# linobit-coilInputs.net
KiCad netlist of a schematic drawn in Altium Designer
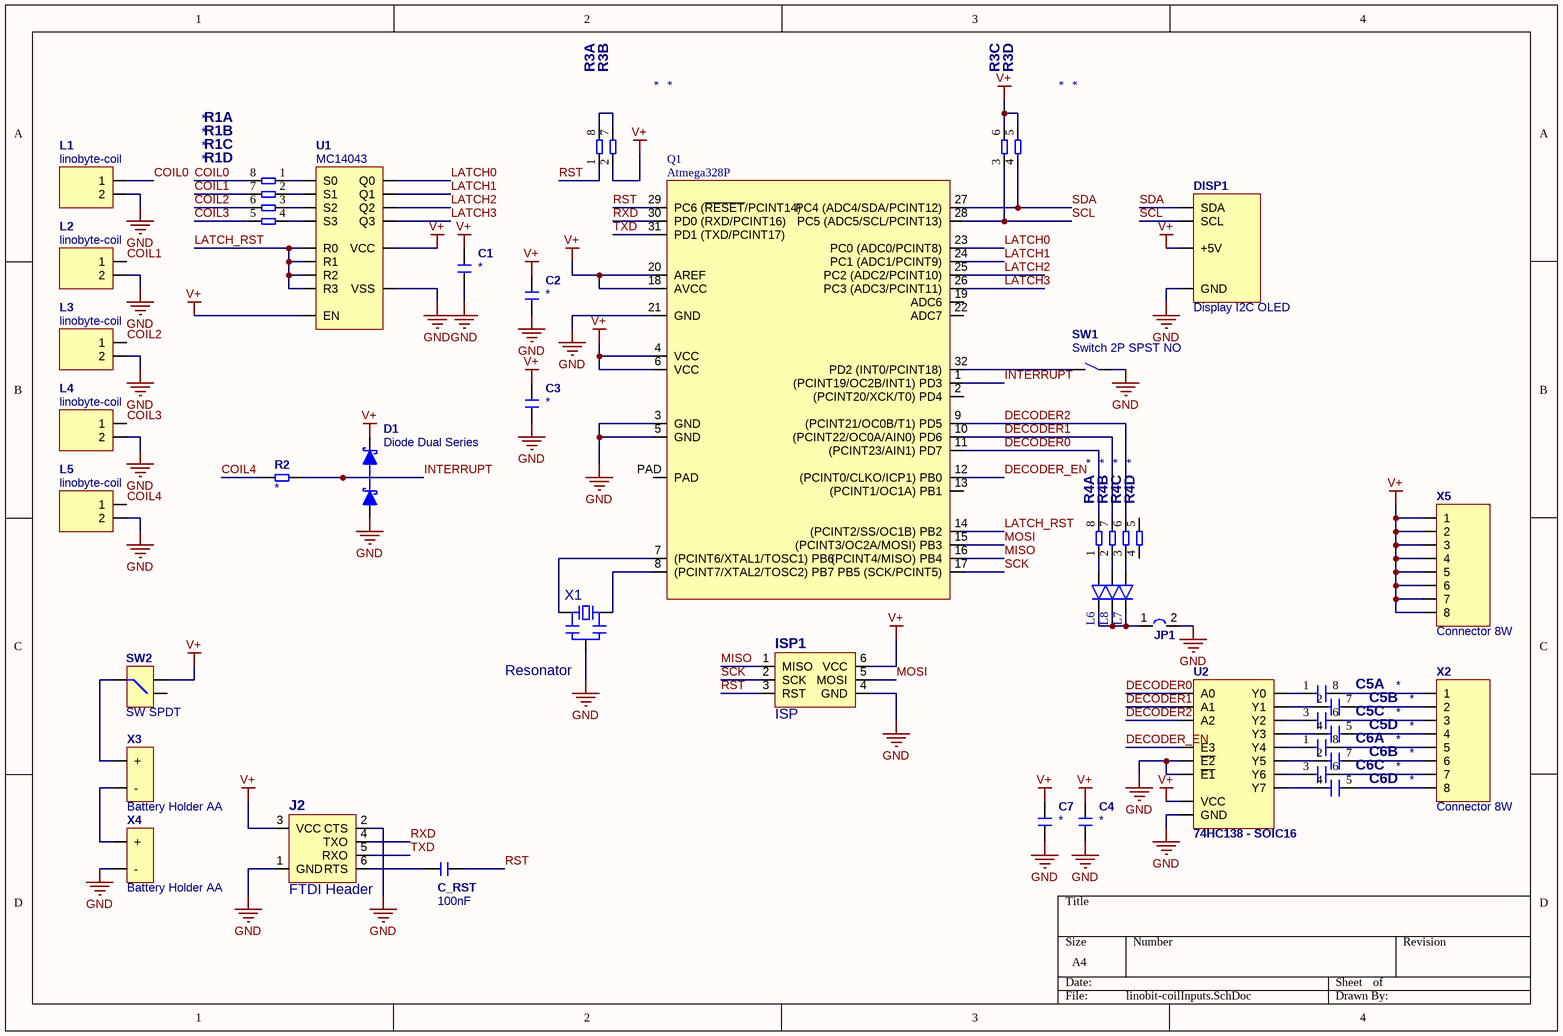
[diagram p0: linobit-coilInputs.SchDoc]

(export (version "E")
  (design (tool "Eeschema 10.0.6"))
  (components
    (comp (ref "C1")
      (value "*")
      (footprint "C0603_N")
      (description "Capacitor MLCC")
      (fields
        (field (name "MANUFACTURER") "Yageo")
        (field (name "MANUFACTURER PART NUMBER") "CC0603KRX7R9BB104")
      )
      (libsource (lib "wes") (part "Capacitor"))
    )
    (comp (ref "C2")
      (value "*")
      (footprint "C0603_N")
      (description "Capacitor MLCC")
      (fields
        (field (name "MANUFACTURER") "Yageo")
        (field (name "MANUFACTURER PART NUMBER") "CC0603KRX7R9BB104")
      )
      (libsource (lib "wes") (part "Capacitor"))
    )
    (comp (ref "C3")
      (value "*")
      (footprint "C0603_N")
      (description "Capacitor MLCC")
      (fields
        (field (name "MANUFACTURER") "Yageo")
        (field (name "MANUFACTURER PART NUMBER") "CC0603KRX7R9BB104")
      )
      (libsource (lib "wes") (part "Capacitor"))
    )
    (comp (ref "C4")
      (value "*")
      (footprint "C0603_N")
      (description "Capacitor MLCC")
      (fields
        (field (name "MANUFACTURER") "Yageo")
        (field (name "MANUFACTURER PART NUMBER") "CC0603KRX7R9BB104")
      )
      (libsource (lib "wes") (part "Capacitor"))
    )
    (comp (ref "C5")
      (value "; *")
      (footprint "C0612 Array 4 Caps")
      (fields (field (name "ALTIUM_VALUE") "*"))
      (libsource (lib "wes") (part "Capacitor Array - 4P"))
    )
    (comp (ref "C6")
      (value "; *")
      (footprint "C0612 Array 4 Caps")
      (fields (field (name "ALTIUM_VALUE") "*"))
      (libsource (lib "wes") (part "Capacitor Array - 4P"))
    )
    (comp (ref "C7")
      (value "*")
      (footprint "C0603_N")
      (description "Capacitor MLCC")
      (fields
        (field (name "MANUFACTURER") "Yageo")
        (field (name "MANUFACTURER PART NUMBER") "CC0603KRX7R9BB104")
      )
      (libsource (lib "wes") (part "Capacitor"))
    )
    (comp (ref "C_RST")
      (value "100nF")
      (footprint "C0603_N")
      (description "Capacitor MLCC")
      (fields
        (field (name "MANUFACTURER") "Yageo")
        (field (name "MANUFACTURER PART NUMBER") "CC0603KRX7R9BB104")
      )
      (libsource (lib "wes") (part "Capacitor"))
    )
    (comp (ref "D1")
      (value "Diode Dual Series")
      (footprint "SOT23_N")
      (libsource (lib "wes") (part "Diode Dual Series"))
    )
    (comp (ref "DISP1")
      (value "Display I2C OLED")
      (footprint "Display OLED 128x64 0.96in")
      (libsource (lib "wes") (part "Display I2C OLED"))
    )
    (comp (ref "ISP1") (value "ISP") (footprint "ISP PTH") (libsource (lib "wes") (part "ISP")))
    (comp (ref "J2")
      (value "FTDI Header")
      (footprint "Header 5W SMD 0.1\"")
      (libsource (lib "wes") (part "FTDI Header"))
    )
    (comp (ref "JP1")
      (value "Jumper 2W")
      (footprint "Jumper SMD 2W NO")
      (libsource (lib "wes") (part "Jumper 2W"))
    )
    (comp (ref "L1")
      (value "linobyte-coil")
      (footprint "linobyte-coil")
      (libsource (lib "wes") (part "linobyte-coil"))
    )
    (comp (ref "L2")
      (value "linobyte-coil")
      (footprint "linobyte-coil")
      (libsource (lib "wes") (part "linobyte-coil"))
    )
    (comp (ref "L3")
      (value "linobyte-coil")
      (footprint "linobyte-coil")
      (libsource (lib "wes") (part "linobyte-coil"))
    )
    (comp (ref "L4")
      (value "linobyte-coil")
      (footprint "linobyte-coil")
      (libsource (lib "wes") (part "linobyte-coil"))
    )
    (comp (ref "L5")
      (value "linobyte-coil")
      (footprint "linobyte-coil")
      (libsource (lib "wes") (part "linobyte-coil"))
    )
    (comp (ref "L6") (value "LED") (footprint "LED 0603/1608") (libsource (lib "wes") (part "LED")))
    (comp (ref "L7") (value "LED") (footprint "LED 0603/1608") (libsource (lib "wes") (part "LED")))
    (comp (ref "L8") (value "LED") (footprint "LED 0603/1608") (libsource (lib "wes") (part "LED")))
    (comp (ref "Q1") (value "Atmega328P") (footprint "TQFP32") (libsource (lib "wes") (part "Atmega328P")))
    (comp (ref "R1")
      (value "; *")
      (footprint "YC164")
      (fields (field (name "ALTIUM_VALUE") "*"))
      (libsource (lib "wes") (part "Resistor Array - 4P"))
    )
    (comp (ref "R2")
      (value "*")
      (footprint "R0603")
      (fields (field (name "ALTIUM_VALUE") "*") (field (name "PUBLISHER") "Altium Limited"))
      (libsource (lib "wes") (part "Resistor"))
    )
    (comp (ref "R3")
      (value "; *")
      (footprint "YC164")
      (fields (field (name "ALTIUM_VALUE") "*"))
      (libsource (lib "wes") (part "Resistor Array - 4P"))
    )
    (comp (ref "R4")
      (value "; *")
      (footprint "YC164")
      (fields (field (name "ALTIUM_VALUE") "*"))
      (libsource (lib "wes") (part "Resistor Array - 4P"))
    )
    (comp (ref "SW1")
      (value "Switch 2P SPST NO")
      (footprint "TACT FSMSM")
      (libsource (lib "wes") (part "Switch 2P SPST NO"))
    )
    (comp (ref "SW2")
      (value "SW SPDT")
      (footprint "SW SPDT JS102011SAQN")
      (libsource (lib "wes") (part "SW SPDT"))
    )
    (comp (ref "U1") (value "MC14043") (footprint "SOIC16") (libsource (lib "wes") (part "MC14043")))
    (comp (ref "U2")
      (value "74HC138 - SOIC16")
      (footprint "SOIC16")
      (libsource (lib "wes") (part "74HC138 - SOIC16"))
    )
    (comp (ref "X1") (value "Resonator") (footprint "Resonator") (libsource (lib "wes") (part "Resonator")))
    (comp (ref "X2")
      (value "Connector 8W")
      (footprint "BCS-108-L-S-PE")
      (libsource (lib "wes") (part "Connector 8W"))
    )
    (comp (ref "X3")
      (value "Battery Holder AA")
      (footprint "Battery Holder AA")
      (libsource (lib "wes") (part "Battery Holder AA"))
    )
    (comp (ref "X4")
      (value "Battery Holder AA")
      (footprint "Battery Holder AA")
      (libsource (lib "wes") (part "Battery Holder AA"))
    )
    (comp (ref "X5")
      (value "Connector 8W")
      (footprint "BCS-108-L-S-PE")
      (libsource (lib "wes") (part "Connector 8W"))
    )
  )
  (nets
    (net (code "1") (name "/COIL0") (class "Default")
      (node (ref "L1") (pin "1") (pinfunction "1_1") (pintype "passive"))
      (node (ref "R1") (pin "8") (pinfunction "8_8") (pintype "passive"))
    )
    (net (code "2") (name "/COIL1") (class "Default")
      (node (ref "L2") (pin "1") (pinfunction "1_1") (pintype "passive"))
      (node (ref "R1") (pin "7") (pinfunction "7_7") (pintype "passive"))
    )
    (net (code "3") (name "/COIL2") (class "Default")
      (node (ref "L3") (pin "1") (pinfunction "1_1") (pintype "passive"))
      (node (ref "R1") (pin "6") (pinfunction "6_6") (pintype "passive"))
    )
    (net (code "4") (name "/COIL3") (class "Default")
      (node (ref "L4") (pin "1") (pinfunction "1_1") (pintype "passive"))
      (node (ref "R1") (pin "5") (pinfunction "5_5") (pintype "passive"))
    )
    (net (code "5") (name "/COIL4") (class "Default")
      (node (ref "L5") (pin "1") (pinfunction "1_1") (pintype "passive"))
      (node (ref "R2") (pin "1") (pinfunction "1_1") (pintype "passive"))
    )
    (net (code "6") (name "/DECODER0") (class "Default")
      (node (ref "Q1") (pin "11") (pinfunction "(PCINT23/AIN1)_PD7_11") (pintype "power_in"))
      (node (ref "R4") (pin "8") (pinfunction "8_8") (pintype "passive"))
      (node (ref "U2") (pin "1") (pinfunction "A0_1") (pintype "power_in"))
    )
    (net (code "7") (name "/DECODER1") (class "Default")
      (node (ref "Q1") (pin "10") (pinfunction "(PCINT22/OC0A/AIN0)_PD6_10") (pintype "power_in"))
      (node (ref "R4") (pin "7") (pinfunction "7_7") (pintype "passive"))
      (node (ref "U2") (pin "2") (pinfunction "A1_2") (pintype "power_in"))
    )
    (net (code "8") (name "/DECODER2") (class "Default")
      (node (ref "Q1") (pin "9") (pinfunction "(PCINT21/OC0B/T1)_PD5_9") (pintype "power_in"))
      (node (ref "R4") (pin "6") (pinfunction "6_6") (pintype "passive"))
      (node (ref "U2") (pin "3") (pinfunction "A2_3") (pintype "power_in"))
    )
    (net (code "9") (name "/DECODER_EN") (class "Default")
      (node (ref "Q1") (pin "12") (pinfunction "(PCINT0/CLKO/ICP1)_PB0_12") (pintype "power_in"))
      (node (ref "U2") (pin "5") (pinfunction "E3_5") (pintype "power_in"))
    )
    (net (code "10") (name "/INTERRUPT") (class "Default")
      (node (ref "D1") (pin "3") (pinfunction "A_3") (pintype "passive"))
      (node (ref "Q1") (pin "1") (pinfunction "(PCINT19/OC2B/INT1)_PD3_1") (pintype "power_in"))
      (node (ref "R2") (pin "2") (pinfunction "2_2") (pintype "passive"))
    )
    (net (code "11") (name "/LATCH0") (class "Default")
      (node (ref "Q1") (pin "23") (pinfunction "PC0_(ADC0/PCINT8)_23") (pintype "power_in"))
      (node (ref "U1") (pin "2") (pinfunction "Q0_2") (pintype "passive"))
    )
    (net (code "12") (name "/LATCH1") (class "Default")
      (node (ref "Q1") (pin "24") (pinfunction "PC1_(ADC1/PCINT9)_24") (pintype "power_in"))
      (node (ref "U1") (pin "9") (pinfunction "Q1_9") (pintype "passive"))
    )
    (net (code "13") (name "/LATCH2") (class "Default")
      (node (ref "Q1") (pin "25") (pinfunction "PC2_(ADC2/PCINT10)_25") (pintype "power_in"))
      (node (ref "U1") (pin "10") (pinfunction "Q2_10") (pintype "passive"))
    )
    (net (code "14") (name "/LATCH3") (class "Default")
      (node (ref "Q1") (pin "26") (pinfunction "PC3_(ADC3/PCINT11)_26") (pintype "power_in"))
      (node (ref "U1") (pin "1") (pinfunction "Q3_1") (pintype "passive"))
    )
    (net (code "15") (name "/LATCH_RST") (class "Default")
      (node (ref "Q1") (pin "14") (pinfunction "(PCINT2/SS/OC1B)_PB2_14") (pintype "power_in"))
      (node (ref "U1") (pin "11") (pinfunction "R2_11") (pintype "passive"))
      (node (ref "U1") (pin "15") (pinfunction "R3_15") (pintype "passive"))
      (node (ref "U1") (pin "3") (pinfunction "R0_3") (pintype "passive"))
      (node (ref "U1") (pin "7") (pinfunction "R1_7") (pintype "passive"))
    )
    (net (code "16") (name "/MISO") (class "Default")
      (node (ref "ISP1") (pin "1") (pinfunction "MISO_1") (pintype "passive"))
      (node (ref "Q1") (pin "16") (pinfunction "(PCINT4/MISO)_PB4_16") (pintype "power_in"))
    )
    (net (code "17") (name "/MOSI") (class "Default")
      (node (ref "ISP1") (pin "5") (pinfunction "MOSI_5") (pintype "passive"))
      (node (ref "Q1") (pin "15") (pinfunction "(PCINT3/OC2A/MOSI)_PB3_15") (pintype "power_in"))
    )
    (net (code "18") (name "/RST") (class "Default")
      (node (ref "C_RST") (pin "2") (pintype "passive"))
      (node (ref "ISP1") (pin "3") (pinfunction "RST_3") (pintype "passive"))
      (node (ref "Q1") (pin "29") (pinfunction "PC6_(~{RESET}/PCINT14)_29") (pintype "power_in"))
      (node (ref "R3") (pin "1") (pinfunction "1_1") (pintype "passive"))
    )
    (net (code "19") (name "/RXD") (class "Default")
      (node (ref "J2") (pin "4") (pinfunction "TXO_4") (pintype "passive"))
      (node (ref "Q1") (pin "30") (pinfunction "PD0_(RXD/PCINT16)_30") (pintype "power_in"))
    )
    (net (code "20") (name "/SCK") (class "Default")
      (node (ref "ISP1") (pin "2") (pinfunction "SCK_2") (pintype "passive"))
      (node (ref "Q1") (pin "17") (pinfunction "PB5_(SCK/PCINT5)_17") (pintype "power_in"))
    )
    (net (code "21") (name "/SCL") (class "Default")
      (node (ref "DISP1") (pin "3") (pinfunction "SCL_3") (pintype "passive"))
      (node (ref "Q1") (pin "28") (pinfunction "PC5_(ADC5/SCL/PCINT13)_28") (pintype "power_in"))
      (node (ref "R3") (pin "3") (pinfunction "3_3") (pintype "passive"))
    )
    (net (code "22") (name "/SDA") (class "Default")
      (node (ref "DISP1") (pin "4") (pinfunction "SDA_4") (pintype "passive"))
      (node (ref "Q1") (pin "27") (pinfunction "PC4_(ADC4/SDA/PCINT12)_27") (pintype "power_in"))
      (node (ref "R3") (pin "4") (pinfunction "4_4") (pintype "passive"))
    )
    (net (code "23") (name "/TXD") (class "Default")
      (node (ref "J2") (pin "5") (pinfunction "RXO_5") (pintype "passive"))
      (node (ref "Q1") (pin "31") (pinfunction "PD1_(TXD/PCINT17)_31") (pintype "power_in"))
    )
    (net (code "24") (name "GND") (class "Default")
      (node (ref "C1") (pin "2") (pintype "passive"))
      (node (ref "C2") (pin "2") (pintype "passive"))
      (node (ref "C3") (pin "2") (pintype "passive"))
      (node (ref "C4") (pin "2") (pintype "passive"))
      (node (ref "C7") (pin "2") (pintype "passive"))
      (node (ref "D1") (pin "1") (pinfunction "A_1") (pintype "passive"))
      (node (ref "DISP1") (pin "1") (pinfunction "GND_1") (pintype "passive"))
      (node (ref "ISP1") (pin "4") (pinfunction "GND_4") (pintype "passive"))
      (node (ref "J2") (pin "1") (pinfunction "GND_1") (pintype "passive"))
      (node (ref "J2") (pin "2") (pinfunction "CTS_2") (pintype "passive"))
      (node (ref "JP1") (pin "2") (pinfunction "2_2") (pintype "passive"))
      (node (ref "L1") (pin "2") (pinfunction "2_2") (pintype "passive"))
      (node (ref "L2") (pin "2") (pinfunction "2_2") (pintype "passive"))
      (node (ref "L3") (pin "2") (pinfunction "2_2") (pintype "passive"))
      (node (ref "L4") (pin "2") (pinfunction "2_2") (pintype "passive"))
      (node (ref "L5") (pin "2") (pinfunction "2_2") (pintype "passive"))
      (node (ref "Q1") (pin "21") (pinfunction "GND_21") (pintype "power_in"))
      (node (ref "Q1") (pin "3") (pinfunction "GND_3") (pintype "power_in"))
      (node (ref "Q1") (pin "5") (pinfunction "GND_5") (pintype "power_in"))
      (node (ref "SW1") (pin "2") (pinfunction "2_2") (pintype "power_in"))
      (node (ref "U1") (pin "8") (pinfunction "VSS_8") (pintype "passive"))
      (node (ref "U2") (pin "4") (pinfunction "~{E2}_4") (pintype "power_in"))
      (node (ref "U2") (pin "6") (pinfunction "~{E1}_6") (pintype "power_in"))
      (node (ref "U2") (pin "8") (pinfunction "GND_8") (pintype "power_in"))
      (node (ref "X1") (pin "2") (pinfunction "2_2") (pintype "passive"))
      (node (ref "X4") (pin "-") (pinfunction "-_-") (pintype "passive"))
    )
    (net (code "25") (name "Net-(C5-Pad5)") (class "Default")
      (node (ref "C5") (pin "5") (pinfunction "5_5") (pintype "passive"))
      (node (ref "X2") (pin "4") (pinfunction "4_4") (pintype "passive"))
    )
    (net (code "26") (name "Net-(C5-Pad6)") (class "Default")
      (node (ref "C5") (pin "6") (pinfunction "6_6") (pintype "passive"))
      (node (ref "X2") (pin "3") (pinfunction "3_3") (pintype "passive"))
    )
    (net (code "27") (name "Net-(C5-Pad7)") (class "Default")
      (node (ref "C5") (pin "7") (pinfunction "7_7") (pintype "passive"))
      (node (ref "X2") (pin "2") (pinfunction "2_2") (pintype "passive"))
    )
    (net (code "28") (name "Net-(C5-Pad8)") (class "Default")
      (node (ref "C5") (pin "8") (pinfunction "8_8") (pintype "passive"))
      (node (ref "X2") (pin "1") (pinfunction "1_1") (pintype "passive"))
    )
    (net (code "29") (name "Net-(C6-Pad5)") (class "Default")
      (node (ref "C6") (pin "5") (pinfunction "5_5") (pintype "passive"))
      (node (ref "X2") (pin "8") (pinfunction "8_8") (pintype "passive"))
    )
    (net (code "30") (name "Net-(C6-Pad6)") (class "Default")
      (node (ref "C6") (pin "6") (pinfunction "6_6") (pintype "passive"))
      (node (ref "X2") (pin "7") (pinfunction "7_7") (pintype "passive"))
    )
    (net (code "31") (name "Net-(C6-Pad7)") (class "Default")
      (node (ref "C6") (pin "7") (pinfunction "7_7") (pintype "passive"))
      (node (ref "X2") (pin "6") (pinfunction "6_6") (pintype "passive"))
    )
    (net (code "32") (name "Net-(C6-Pad8)") (class "Default")
      (node (ref "C6") (pin "8") (pinfunction "8_8") (pintype "passive"))
      (node (ref "X2") (pin "5") (pinfunction "5_5") (pintype "passive"))
    )
    (net (code "33") (name "Net-(J2-RTS)") (class "Default")
      (node (ref "C_RST") (pin "1") (pintype "passive"))
      (node (ref "J2") (pin "6") (pinfunction "RTS_6") (pintype "passive"))
    )
    (net (code "34") (name "Net-(L6-A)") (class "Default")
      (node (ref "L6") (pin "2") (pinfunction "A_2") (pintype "power_in"))
      (node (ref "R4") (pin "1") (pinfunction "1_1") (pintype "passive"))
    )
    (net (code "35") (name "Net-(L6-K)") (class "Default")
      (node (ref "JP1") (pin "1") (pinfunction "1_1") (pintype "passive"))
      (node (ref "L6") (pin "1") (pinfunction "K_1") (pintype "power_in"))
      (node (ref "L7") (pin "1") (pinfunction "K_1") (pintype "power_in"))
      (node (ref "L8") (pin "1") (pinfunction "K_1") (pintype "power_in"))
    )
    (net (code "36") (name "Net-(L7-A)") (class "Default")
      (node (ref "L7") (pin "2") (pinfunction "A_2") (pintype "power_in"))
      (node (ref "R4") (pin "3") (pinfunction "3_3") (pintype "passive"))
    )
    (net (code "37") (name "Net-(L8-A)") (class "Default")
      (node (ref "L8") (pin "2") (pinfunction "A_2") (pintype "power_in"))
      (node (ref "R4") (pin "2") (pinfunction "2_2") (pintype "passive"))
    )
    (net (code "38") (name "Net-(Q1-(PCINT6{slash}XTAL1{slash}TOSC1)_PB6)") (class "Default")
      (node (ref "Q1") (pin "7") (pinfunction "(PCINT6/XTAL1/TOSC1)_PB6_7") (pintype "power_in"))
      (node (ref "X1") (pin "1") (pinfunction "1_1") (pintype "passive"))
    )
    (net (code "39") (name "Net-(Q1-(PCINT7{slash}XTAL2{slash}TOSC2)_PB7)") (class "Default")
      (node (ref "Q1") (pin "8") (pinfunction "(PCINT7/XTAL2/TOSC2)_PB7_8") (pintype "power_in"))
      (node (ref "X1") (pin "3") (pinfunction "3_3") (pintype "passive"))
    )
    (net (code "40") (name "Net-(Q1-PD2_(INT0{slash}PCINT18))") (class "Default")
      (node (ref "Q1") (pin "32") (pinfunction "PD2_(INT0/PCINT18)_32") (pintype "power_in"))
      (node (ref "SW1") (pin "1") (pinfunction "1_1") (pintype "power_in"))
    )
    (net (code "41") (name "Net-(R3-Pad7)") (class "Default")
      (node (ref "R3") (pin "7") (pinfunction "7_7") (pintype "passive"))
      (node (ref "R3") (pin "8") (pinfunction "8_8") (pintype "passive"))
    )
    (net (code "42") (name "Net-(SW2-Pad2)") (class "Default")
      (node (ref "SW2") (pin "2") (pintype "passive"))
      (node (ref "X3") (pin "+") (pinfunction "+_+") (pintype "passive"))
    )
    (net (code "43") (name "Net-(U1-S0)") (class "Default")
      (node (ref "R1") (pin "1") (pinfunction "1_1") (pintype "passive"))
      (node (ref "U1") (pin "4") (pinfunction "S0_4") (pintype "passive"))
    )
    (net (code "44") (name "Net-(U1-S1)") (class "Default")
      (node (ref "R1") (pin "2") (pinfunction "2_2") (pintype "passive"))
      (node (ref "U1") (pin "6") (pinfunction "S1_6") (pintype "passive"))
    )
    (net (code "45") (name "Net-(U1-S2)") (class "Default")
      (node (ref "R1") (pin "3") (pinfunction "3_3") (pintype "passive"))
      (node (ref "U1") (pin "12") (pinfunction "S2_12") (pintype "passive"))
    )
    (net (code "46") (name "Net-(U1-S3)") (class "Default")
      (node (ref "R1") (pin "4") (pinfunction "4_4") (pintype "passive"))
      (node (ref "U1") (pin "14") (pinfunction "S3_14") (pintype "passive"))
    )
    (net (code "47") (name "Net-(U2-Y0)") (class "Default")
      (node (ref "C5") (pin "1") (pinfunction "1_1") (pintype "passive"))
      (node (ref "U2") (pin "15") (pinfunction "Y0_15") (pintype "power_in"))
    )
    (net (code "48") (name "Net-(U2-Y1)") (class "Default")
      (node (ref "C5") (pin "2") (pinfunction "2_2") (pintype "passive"))
      (node (ref "U2") (pin "14") (pinfunction "Y1_14") (pintype "power_in"))
    )
    (net (code "49") (name "Net-(U2-Y2)") (class "Default")
      (node (ref "C5") (pin "3") (pinfunction "3_3") (pintype "passive"))
      (node (ref "U2") (pin "13") (pinfunction "Y2_13") (pintype "power_in"))
    )
    (net (code "50") (name "Net-(U2-Y3)") (class "Default")
      (node (ref "C5") (pin "4") (pinfunction "4_4") (pintype "passive"))
      (node (ref "U2") (pin "12") (pinfunction "Y3_12") (pintype "power_in"))
    )
    (net (code "51") (name "Net-(U2-Y4)") (class "Default")
      (node (ref "C6") (pin "1") (pinfunction "1_1") (pintype "passive"))
      (node (ref "U2") (pin "11") (pinfunction "Y4_11") (pintype "power_in"))
    )
    (net (code "52") (name "Net-(U2-Y5)") (class "Default")
      (node (ref "C6") (pin "2") (pinfunction "2_2") (pintype "passive"))
      (node (ref "U2") (pin "10") (pinfunction "Y5_10") (pintype "power_in"))
    )
    (net (code "53") (name "Net-(U2-Y6)") (class "Default")
      (node (ref "C6") (pin "3") (pinfunction "3_3") (pintype "passive"))
      (node (ref "U2") (pin "9") (pinfunction "Y6_9") (pintype "power_in"))
    )
    (net (code "54") (name "Net-(U2-Y7)") (class "Default")
      (node (ref "C6") (pin "4") (pinfunction "4_4") (pintype "passive"))
      (node (ref "U2") (pin "7") (pinfunction "Y7_7") (pintype "power_in"))
    )
    (net (code "55") (name "Net-(X3-Pad-)") (class "Default")
      (node (ref "X3") (pin "-") (pinfunction "-_-") (pintype "passive"))
      (node (ref "X4") (pin "+") (pinfunction "+_+") (pintype "passive"))
    )
    (net (code "56") (name "V+") (class "Default")
      (node (ref "C1") (pin "1") (pintype "passive"))
      (node (ref "C2") (pin "1") (pintype "passive"))
      (node (ref "C3") (pin "1") (pintype "passive"))
      (node (ref "C4") (pin "1") (pintype "passive"))
      (node (ref "C7") (pin "1") (pintype "passive"))
      (node (ref "D1") (pin "2") (pinfunction "K_2") (pintype "passive"))
      (node (ref "DISP1") (pin "2") (pinfunction "+5V_2") (pintype "passive"))
      (node (ref "ISP1") (pin "6") (pinfunction "VCC_6") (pintype "passive"))
      (node (ref "J2") (pin "3") (pinfunction "VCC_3") (pintype "passive"))
      (node (ref "Q1") (pin "18") (pinfunction "AVCC_18") (pintype "power_in"))
      (node (ref "Q1") (pin "20") (pinfunction "AREF_20") (pintype "power_in"))
      (node (ref "Q1") (pin "4") (pinfunction "VCC_4") (pintype "power_in"))
      (node (ref "Q1") (pin "6") (pinfunction "VCC_6") (pintype "power_in"))
      (node (ref "R3") (pin "2") (pinfunction "2_2") (pintype "passive"))
      (node (ref "R3") (pin "5") (pinfunction "5_5") (pintype "passive"))
      (node (ref "R3") (pin "6") (pinfunction "6_6") (pintype "passive"))
      (node (ref "SW2") (pin "1") (pintype "passive"))
      (node (ref "U1") (pin "16") (pinfunction "VCC_16") (pintype "passive"))
      (node (ref "U1") (pin "5") (pinfunction "EN_5") (pintype "passive"))
      (node (ref "U2") (pin "16") (pinfunction "VCC_16") (pintype "power_in"))
      (node (ref "X5") (pin "1") (pinfunction "1_1") (pintype "passive"))
      (node (ref "X5") (pin "2") (pinfunction "2_2") (pintype "passive"))
      (node (ref "X5") (pin "3") (pinfunction "3_3") (pintype "passive"))
      (node (ref "X5") (pin "4") (pinfunction "4_4") (pintype "passive"))
      (node (ref "X5") (pin "5") (pinfunction "5_5") (pintype "passive"))
      (node (ref "X5") (pin "6") (pinfunction "6_6") (pintype "passive"))
      (node (ref "X5") (pin "7") (pinfunction "7_7") (pintype "passive"))
      (node (ref "X5") (pin "8") (pinfunction "8_8") (pintype "passive"))
    )
    (net (code "57") (name "unconnected-(Q1-(PCINT1{slash}OC1A)_PB1-Pad13)") (class "Default")
      (node (ref "Q1") (pin "13") (pinfunction "(PCINT1/OC1A)_PB1_13") (pintype "power_in"))
    )
    (net (code "58") (name "unconnected-(Q1-(PCINT20{slash}XCK{slash}T0)_PD4-Pad2)") (class "Default")
      (node (ref "Q1") (pin "2") (pinfunction "(PCINT20/XCK/T0)_PD4_2") (pintype "power_in"))
    )
    (net (code "59") (name "unconnected-(Q1-ADC6-Pad19)") (class "Default")
      (node (ref "Q1") (pin "19") (pinfunction "ADC6_19") (pintype "power_in"))
    )
    (net (code "60") (name "unconnected-(Q1-ADC7-Pad22)") (class "Default")
      (node (ref "Q1") (pin "22") (pinfunction "ADC7_22") (pintype "power_in"))
    )
    (net (code "61") (name "unconnected-(Q1-PadPAD)") (class "Default")
      (node (ref "Q1") (pin "PAD") (pinfunction "PAD_PAD") (pintype "power_in"))
    )
    (net (code "62") (name "unconnected-(R4-Pad4)") (class "Default")
      (node (ref "R4") (pin "4") (pinfunction "4_4") (pintype "passive"))
    )
    (net (code "63") (name "unconnected-(R4-Pad5)") (class "Default")
      (node (ref "R4") (pin "5") (pinfunction "5_5") (pintype "passive"))
    )
    (net (code "64") (name "unconnected-(SW2-Pad3)") (class "Default")
      (node (ref "SW2") (pin "3") (pintype "passive"))
    )
  )
)
